# Power_Supply_9V.net
KiCad netlist of a schematic drawn in Altium Designer
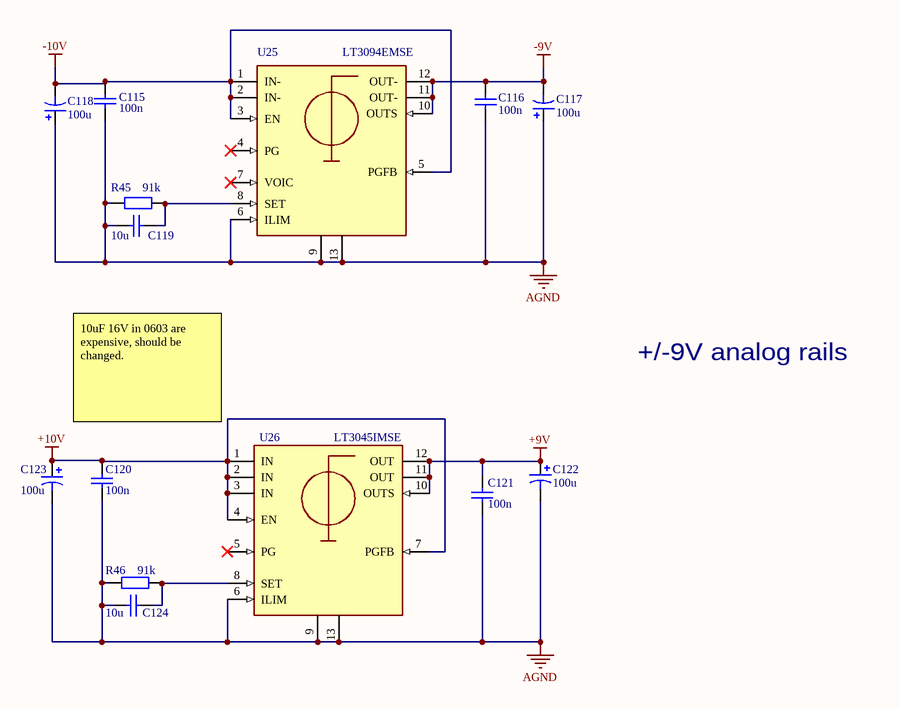
[diagram p0: Power_Supply_9V.SchDoc]

(export (version "E")
  (design (tool "Eeschema 10.0.6"))
  (components
    (comp (ref "C115")
      (value "100n")
      (footprint "PCB-rf0pzaa82dpbeu9l4sxm-1")
      (description "Capacitor 0603")
      (fields (field (name "LCSC PART #") "C14663") (field (name "LCSC PART #_1") "C109474"))
      (libsource (lib "FavoritesLibrary") (part "SYM-x8hddryxw4o380xfi98v-1"))
    )
    (comp (ref "C116")
      (value "100n")
      (footprint "PCB-rf0pzaa82dpbeu9l4sxm-1")
      (description "Capacitor 0603")
      (fields (field (name "LCSC PART #") "C14663") (field (name "LCSC PART #_1") "C109474"))
      (libsource (lib "FavoritesLibrary") (part "SYM-x8hddryxw4o380xfi98v-1"))
    )
    (comp (ref "C117")
      (value "100u")
      (footprint "PCB-9bfrndi9huxo1n7cihpl-1")
      (description "In a Pack of 25, KEMET 100?F Electrolytic Capacitor 10V dc Through Hole - A758EK107M1AAAE016")
      (fields (field (name "MANUFACTURER PART NUMBER") "A758EK107M1AAAE016"))
      (libsource (lib "FavoritesLibrary") (part "SYM-6546a831a81eba81-3"))
    )
    (comp (ref "C118")
      (value "100u")
      (footprint "PCB-9bfrndi9huxo1n7cihpl-1")
      (description "In a Pack of 25, KEMET 100?F Electrolytic Capacitor 10V dc Through Hole - A758EK107M1AAAE016")
      (fields (field (name "MANUFACTURER PART NUMBER") "A758EK107M1AAAE016"))
      (libsource (lib "FavoritesLibrary") (part "SYM-6546a831a81eba81-3"))
    )
    (comp (ref "C119")
      (value "10u")
      (footprint "PCB-rf0pzaa82dpbeu9l4sxm-1")
      (description "Capacitor 0603")
      (fields (field (name "LCSC PART #") "C19702") (field (name "LCSC PART #_1") "C25804"))
      (libsource (lib "FavoritesLibrary") (part "SYM-x8hddryxw4o380xfi98v-1"))
    )
    (comp (ref "C120")
      (value "100n")
      (footprint "PCB-rf0pzaa82dpbeu9l4sxm-1")
      (description "Capacitor 0603")
      (fields (field (name "LCSC PART #") "C14663") (field (name "LCSC PART #_1") "C109474"))
      (libsource (lib "FavoritesLibrary") (part "SYM-x8hddryxw4o380xfi98v-1"))
    )
    (comp (ref "C121")
      (value "100n")
      (footprint "PCB-rf0pzaa82dpbeu9l4sxm-1")
      (description "Capacitor 0603")
      (fields (field (name "LCSC PART #") "C14663") (field (name "LCSC PART #_1") "C109474"))
      (libsource (lib "FavoritesLibrary") (part "SYM-x8hddryxw4o380xfi98v-1"))
    )
    (comp (ref "C122")
      (value "100u")
      (footprint "PCB-9bfrndi9huxo1n7cihpl-1")
      (description "In a Pack of 25, KEMET 100?F Electrolytic Capacitor 10V dc Through Hole - A758EK107M1AAAE016")
      (fields (field (name "MANUFACTURER PART NUMBER") "A758EK107M1AAAE016"))
      (libsource (lib "FavoritesLibrary") (part "SYM-6546a831a81eba81-3"))
    )
    (comp (ref "C123")
      (value "100u")
      (footprint "PCB-9bfrndi9huxo1n7cihpl-1")
      (description "In a Pack of 25, KEMET 100?F Electrolytic Capacitor 10V dc Through Hole - A758EK107M1AAAE016")
      (fields (field (name "MANUFACTURER PART NUMBER") "A758EK107M1AAAE016"))
      (libsource (lib "FavoritesLibrary") (part "SYM-6546a831a81eba81-3"))
    )
    (comp (ref "C124")
      (value "10u")
      (footprint "PCB-rf0pzaa82dpbeu9l4sxm-1")
      (description "Capacitor 0603")
      (fields (field (name "LCSC PART #") "C19702") (field (name "LCSC PART #_1") "C25804"))
      (libsource (lib "FavoritesLibrary") (part "SYM-x8hddryxw4o380xfi98v-1"))
    )
    (comp (ref "R45")
      (value "91k")
      (footprint "PCB-3d5y3t7f8drf35yjcj59-1")
      (description "Resistor 0603")
      (fields (field (name "LCSC PART #") "C23265") (field (name "LCSC PART #_1") "C23345"))
      (libsource (lib "FavoritesLibrary") (part "SYM-xcu3s4ikiffkkgbeyow5-1"))
    )
    (comp (ref "R46")
      (value "91k")
      (footprint "PCB-3d5y3t7f8drf35yjcj59-1")
      (description "Resistor 0603")
      (fields (field (name "LCSC PART #") "C23265") (field (name "LCSC PART #_1") "C23345"))
      (libsource (lib "FavoritesLibrary") (part "SYM-xcu3s4ikiffkkgbeyow5-1"))
    )
    (comp (ref "U25")
      (value "LT3094EMSE")
      (footprint "PCB-wizual0g3wynqnqrtsvy-1")
      (description "LDO Regulator Neg 0V to -19.5V 0.5A 12-Pin MSOP EP Tube")
      (fields (field (name "MANUFACTURER PART NUMBER") "LT3094EMSE#PBF"))
      (libsource (lib "FavoritesLibrary") (part "SYM-a88b642e33ab774c-3"))
    )
    (comp (ref "U26")
      (value "LT3045IMSE")
      (footprint "PCB-wov5llpgebpq1pwypz48-1")
      (description "LDO Regulator Pos 0V to 20V 0.5A Automotive 12-Pin MSOP EP Tube")
      (fields (field (name "MANUFACTURER PART NUMBER") "LT3045IMSE#PBF"))
      (libsource (lib "FavoritesLibrary") (part "SYM-53899e0384ae8c4e-7"))
    )
  )
  (nets
    (net (code "1") (name "+9V") (class "Default")
      (node (ref "C121") (pin "2") (pinfunction "2_2") (pintype "passive"))
      (node (ref "C122") (pin "1") (pinfunction "1_1") (pintype "passive"))
      (node (ref "U26") (pin "10") (pinfunction "OUTS_10") (pintype "input"))
      (node (ref "U26") (pin "11") (pinfunction "OUT_11") (pintype "power_in"))
      (node (ref "U26") (pin "12") (pinfunction "OUT_12") (pintype "power_in"))
    )
    (net (code "2") (name "+10V") (class "Default")
      (node (ref "C120") (pin "2") (pinfunction "2_2") (pintype "passive"))
      (node (ref "C123") (pin "1") (pinfunction "1_1") (pintype "passive"))
      (node (ref "U26") (pin "1") (pinfunction "IN_1") (pintype "power_in"))
      (node (ref "U26") (pin "2") (pinfunction "IN_2") (pintype "power_in"))
      (node (ref "U26") (pin "3") (pinfunction "IN_3") (pintype "power_in"))
      (node (ref "U26") (pin "4") (pinfunction "EN_4") (pintype "input"))
      (node (ref "U26") (pin "7") (pinfunction "PGFB_7") (pintype "input"))
    )
    (net (code "3") (name "-9V") (class "Default")
      (node (ref "C116") (pin "2") (pinfunction "2_2") (pintype "passive"))
      (node (ref "C117") (pin "2") (pinfunction "2_2") (pintype "passive"))
      (node (ref "U25") (pin "10") (pinfunction "OUTS_10") (pintype "input"))
      (node (ref "U25") (pin "11") (pinfunction "OUT-_11") (pintype "power_in"))
      (node (ref "U25") (pin "12") (pinfunction "OUT-_12") (pintype "power_in"))
    )
    (net (code "4") (name "-10V") (class "Default")
      (node (ref "C115") (pin "2") (pinfunction "2_2") (pintype "passive"))
      (node (ref "C118") (pin "2") (pinfunction "2_2") (pintype "passive"))
      (node (ref "U25") (pin "1") (pinfunction "IN-_1") (pintype "power_in"))
      (node (ref "U25") (pin "2") (pinfunction "IN-_2") (pintype "power_in"))
      (node (ref "U25") (pin "3") (pinfunction "EN_3") (pintype "input"))
      (node (ref "U25") (pin "5") (pinfunction "PGFB_5") (pintype "input"))
    )
    (net (code "5") (name "AGND") (class "Default")
      (node (ref "C115") (pin "1") (pinfunction "1_1") (pintype "passive"))
      (node (ref "C116") (pin "1") (pinfunction "1_1") (pintype "passive"))
      (node (ref "C117") (pin "1") (pinfunction "1_1") (pintype "passive"))
      (node (ref "C118") (pin "1") (pinfunction "1_1") (pintype "passive"))
      (node (ref "C119") (pin "2") (pinfunction "2_2") (pintype "passive"))
      (node (ref "C120") (pin "1") (pinfunction "1_1") (pintype "passive"))
      (node (ref "C121") (pin "1") (pinfunction "1_1") (pintype "passive"))
      (node (ref "C122") (pin "2") (pinfunction "2_2") (pintype "passive"))
      (node (ref "C123") (pin "2") (pinfunction "2_2") (pintype "passive"))
      (node (ref "C124") (pin "2") (pinfunction "2_2") (pintype "passive"))
      (node (ref "R45") (pin "2") (pinfunction "2_2") (pintype "passive"))
      (node (ref "R46") (pin "2") (pinfunction "2_2") (pintype "passive"))
      (node (ref "U25") (pin "13") (pinfunction "GND_13") (pintype "power_in"))
      (node (ref "U25") (pin "6") (pinfunction "ILIM_6") (pintype "input"))
      (node (ref "U25") (pin "9") (pinfunction "GND_9") (pintype "power_in"))
      (node (ref "U26") (pin "13") (pinfunction "GND_13") (pintype "power_in"))
      (node (ref "U26") (pin "6") (pinfunction "ILIM_6") (pintype "input"))
      (node (ref "U26") (pin "9") (pinfunction "GND_9") (pintype "power_in"))
    )
    (net (code "6") (name "Net-(U25-SET)") (class "Default")
      (node (ref "C119") (pin "1") (pinfunction "1_1") (pintype "passive"))
      (node (ref "R45") (pin "1") (pinfunction "1_1") (pintype "passive"))
      (node (ref "U25") (pin "8") (pinfunction "SET_8") (pintype "input"))
    )
    (net (code "7") (name "Net-(U26-SET)") (class "Default")
      (node (ref "C124") (pin "1") (pinfunction "1_1") (pintype "passive"))
      (node (ref "R46") (pin "1") (pinfunction "1_1") (pintype "passive"))
      (node (ref "U26") (pin "8") (pinfunction "SET_8") (pintype "input"))
    )
    (net (code "8") (name "unconnected-(U25-PG-Pad4)") (class "Default")
      (node (ref "U25") (pin "4") (pinfunction "PG_4") (pintype "input+no_connect"))
    )
    (net (code "9") (name "unconnected-(U25-VOIC-Pad7)") (class "Default")
      (node (ref "U25") (pin "7") (pinfunction "VOIC_7") (pintype "input+no_connect"))
    )
    (net (code "10") (name "unconnected-(U26-PG-Pad5)") (class "Default")
      (node (ref "U26") (pin "5") (pinfunction "PG_5") (pintype "input+no_connect"))
    )
  )
)
